# shieldv2.net
KiCad netlist of a schematic drawn in EAGLE
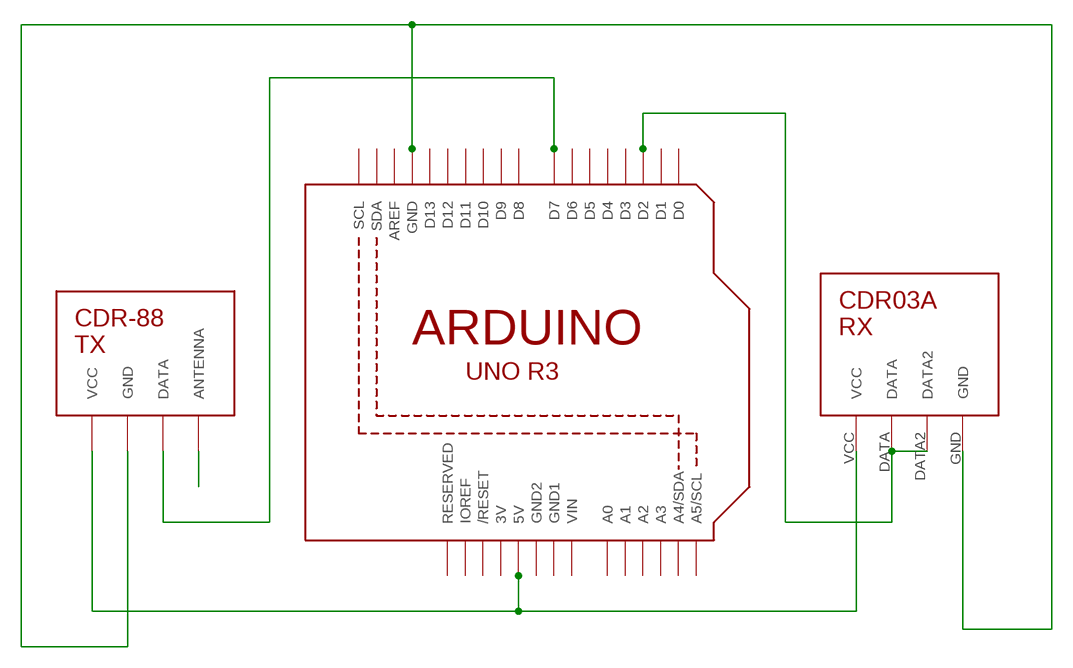
[diagram p0: schematic, sheet 1]

(export (version "E")
  (design (tool "Eeschema 10.0.6"))
  (components
    (comp (ref "U$1")
      (value "CDT-88")
      (footprint "eagle-import:CDT-88")
      (libsource (lib "eagle-import") (part "CDT-88"))
    )
    (comp (ref "U$2")
      (value "CDR03A")
      (footprint "eagle-import:CDR03A")
      (libsource (lib "eagle-import") (part "CDR03A"))
    )
    (comp (ref "U2")
      (value "ARDUINOR3-DIMENSION")
      (footprint "eagle-import:ARDUINOR3")
      (libsource (lib "eagle-import") (part "ARDUINOR3-DIMENSION"))
    )
  )
  (nets
    (net (code "1") (name "/3V") (class "Default")
      (node (ref "U2") (pin "3V") (pinfunction "3V_3V") (pintype "power_in"))
    )
    (net (code "2") (name "/GND1") (class "Default")
      (node (ref "U2") (pin "GND1") (pinfunction "GND1_GND1") (pintype "power_in"))
    )
    (net (code "3") (name "/GND2") (class "Default")
      (node (ref "U2") (pin "GND2") (pinfunction "GND2_GND2") (pintype "power_in"))
    )
    (net (code "4") (name "/VIN") (class "Default")
      (node (ref "U2") (pin "VIN") (pinfunction "VIN_VIN") (pintype "power_in"))
    )
    (net (code "5") (name "Net-(U$1-PadDATA)") (class "Default")
      (node (ref "U$1") (pin "DATA") (pinfunction "DATA_DATA") (pintype "bidirectional"))
      (node (ref "U2") (pin "D7") (pinfunction "D7_D7") (pintype "bidirectional"))
    )
    (net (code "6") (name "Net-(U$1-PadGND)") (class "Default")
      (node (ref "U$1") (pin "GND") (pinfunction "GND_GND") (pintype "bidirectional"))
      (node (ref "U$2") (pin "GND") (pinfunction "GND_GND") (pintype "bidirectional"))
      (node (ref "U2") (pin "GND") (pinfunction "GND_GND") (pintype "power_in"))
    )
    (net (code "7") (name "Net-(U$1-PadVCC)") (class "Default")
      (node (ref "U$1") (pin "VCC") (pinfunction "VCC_VCC") (pintype "bidirectional"))
      (node (ref "U$2") (pin "VCC") (pinfunction "VCC_VCC") (pintype "bidirectional"))
      (node (ref "U2") (pin "5V") (pinfunction "5V_5V") (pintype "power_in"))
    )
    (net (code "8") (name "Net-(U$2-PadDATA)") (class "Default")
      (node (ref "U$2") (pin "DATA") (pinfunction "DATA_DATA") (pintype "bidirectional"))
      (node (ref "U$2") (pin "DATA2") (pinfunction "DATA2_DATA2") (pintype "bidirectional"))
      (node (ref "U2") (pin "D2") (pinfunction "D2_D2") (pintype "bidirectional"))
    )
    (net (code "9") (name "unconnected-(U$1-PadANTENNA)") (class "Default")
      (node (ref "U$1") (pin "ANTENNA") (pinfunction "ANTENNA_ANTENNA") (pintype "bidirectional"))
    )
    (net (code "10") (name "unconnected-(U2-A4{slash}SDA-PadA4)") (class "Default")
      (node (ref "U2") (pin "A4") (pinfunction "A4/SDA_A4") (pintype "bidirectional"))
    )
    (net (code "11") (name "unconnected-(U2-A5{slash}SCL-PadA5)") (class "Default")
      (node (ref "U2") (pin "A5") (pinfunction "A5/SCL_A5") (pintype "bidirectional"))
    )
    (net (code "12") (name "unconnected-(U2-PadA0)") (class "Default")
      (node (ref "U2") (pin "A0") (pinfunction "A0_A0") (pintype "bidirectional"))
    )
    (net (code "13") (name "unconnected-(U2-PadA1)") (class "Default")
      (node (ref "U2") (pin "A1") (pinfunction "A1_A1") (pintype "bidirectional"))
    )
    (net (code "14") (name "unconnected-(U2-PadA2)") (class "Default")
      (node (ref "U2") (pin "A2") (pinfunction "A2_A2") (pintype "bidirectional"))
    )
    (net (code "15") (name "unconnected-(U2-PadA3)") (class "Default")
      (node (ref "U2") (pin "A3") (pinfunction "A3_A3") (pintype "bidirectional"))
    )
    (net (code "16") (name "unconnected-(U2-PadAREF)") (class "Default")
      (node (ref "U2") (pin "AREF") (pinfunction "AREF_AREF") (pintype "bidirectional"))
    )
    (net (code "17") (name "unconnected-(U2-PadD0)") (class "Default")
      (node (ref "U2") (pin "D0") (pinfunction "D0_D0") (pintype "bidirectional"))
    )
    (net (code "18") (name "unconnected-(U2-PadD1)") (class "Default")
      (node (ref "U2") (pin "D1") (pinfunction "D1_D1") (pintype "bidirectional"))
    )
    (net (code "19") (name "unconnected-(U2-PadD3)") (class "Default")
      (node (ref "U2") (pin "D3") (pinfunction "D3_D3") (pintype "bidirectional"))
    )
    (net (code "20") (name "unconnected-(U2-PadD4)") (class "Default")
      (node (ref "U2") (pin "D4") (pinfunction "D4_D4") (pintype "bidirectional"))
    )
    (net (code "21") (name "unconnected-(U2-PadD5)") (class "Default")
      (node (ref "U2") (pin "D5") (pinfunction "D5_D5") (pintype "bidirectional"))
    )
    (net (code "22") (name "unconnected-(U2-PadD6)") (class "Default")
      (node (ref "U2") (pin "D6") (pinfunction "D6_D6") (pintype "bidirectional"))
    )
    (net (code "23") (name "unconnected-(U2-PadD8)") (class "Default")
      (node (ref "U2") (pin "D8") (pinfunction "D8_D8") (pintype "bidirectional"))
    )
    (net (code "24") (name "unconnected-(U2-PadD9)") (class "Default")
      (node (ref "U2") (pin "D9") (pinfunction "D9_D9") (pintype "bidirectional"))
    )
    (net (code "25") (name "unconnected-(U2-PadD10)") (class "Default")
      (node (ref "U2") (pin "D10") (pinfunction "D10_D10") (pintype "bidirectional"))
    )
    (net (code "26") (name "unconnected-(U2-PadD11)") (class "Default")
      (node (ref "U2") (pin "D11") (pinfunction "D11_D11") (pintype "bidirectional"))
    )
    (net (code "27") (name "unconnected-(U2-PadD12)") (class "Default")
      (node (ref "U2") (pin "D12") (pinfunction "D12_D12") (pintype "bidirectional"))
    )
    (net (code "28") (name "unconnected-(U2-PadD13)") (class "Default")
      (node (ref "U2") (pin "D13") (pinfunction "D13_D13") (pintype "bidirectional"))
    )
    (net (code "29") (name "unconnected-(U2-PadIOREF)") (class "Default")
      (node (ref "U2") (pin "IOREF") (pinfunction "IOREF_IOREF") (pintype "output"))
    )
    (net (code "30") (name "unconnected-(U2-PadRESERVED)") (class "Default")
      (node (ref "U2") (pin "RESERVED") (pinfunction "RESERVED_RESERVED") (pintype "no_connect"))
    )
    (net (code "31") (name "unconnected-(U2-PadSCL)") (class "Default")
      (node (ref "U2") (pin "SCL") (pinfunction "SCL_SCL") (pintype "bidirectional"))
    )
    (net (code "32") (name "unconnected-(U2-PadSDA)") (class "Default")
      (node (ref "U2") (pin "SDA") (pinfunction "SDA_SDA") (pintype "bidirectional"))
    )
    (net (code "33") (name "unconnected-(U2-{slash}RESET-PadRESET)") (class "Default")
      (node (ref "U2") (pin "RESET") (pinfunction "/RESET_RESET") (pintype "bidirectional"))
    )
  )
)
